# TML_Tick_Tacho_Timergrapher_Mic_v2.net
KiCad netlist of a schematic drawn in EAGLE
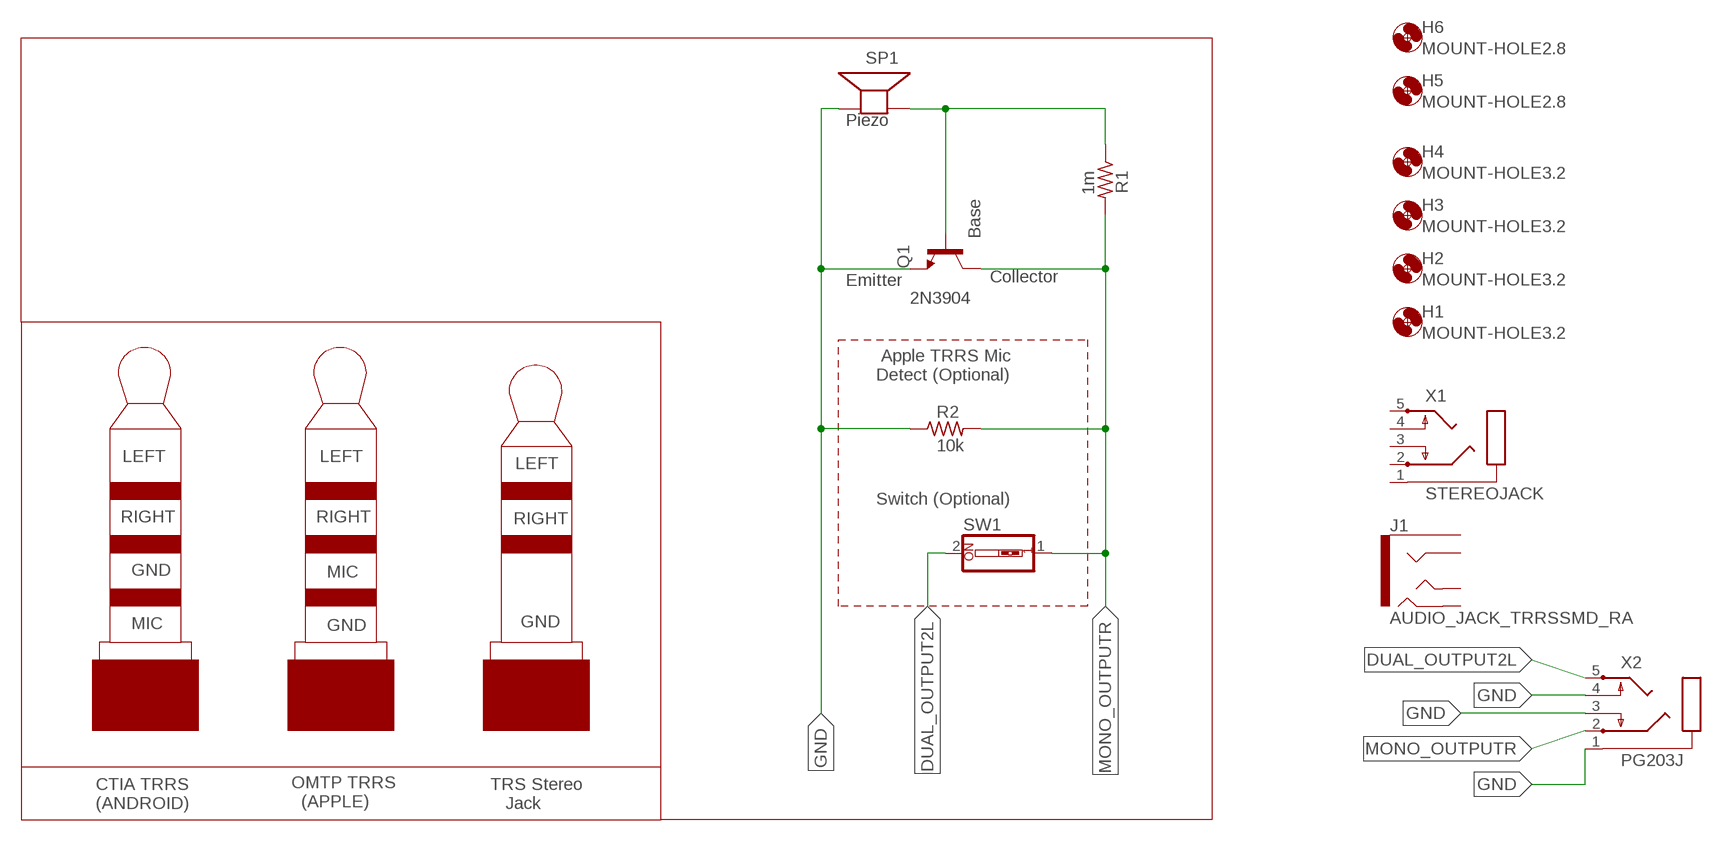
[diagram p0: schematic, sheet 1]

(export (version "E")
  (design (tool "Eeschema 10.0.6"))
  (components
    (comp (ref "H1")
      (value "MOUNT-HOLE3.2")
      (footprint "eagle-import:3,2")
      (libsource (lib "eagle-import") (part "MOUNT-HOLE3.2"))
    )
    (comp (ref "H2")
      (value "MOUNT-HOLE3.2")
      (footprint "eagle-import:3,2")
      (libsource (lib "eagle-import") (part "MOUNT-HOLE3.2"))
    )
    (comp (ref "H3")
      (value "MOUNT-HOLE3.2")
      (footprint "eagle-import:3,2")
      (libsource (lib "eagle-import") (part "MOUNT-HOLE3.2"))
    )
    (comp (ref "H4")
      (value "MOUNT-HOLE3.2")
      (footprint "eagle-import:3,2")
      (libsource (lib "eagle-import") (part "MOUNT-HOLE3.2"))
    )
    (comp (ref "H5")
      (value "MOUNT-HOLE2.8")
      (footprint "eagle-import:2,8")
      (libsource (lib "eagle-import") (part "MOUNT-HOLE2.8"))
    )
    (comp (ref "H6")
      (value "MOUNT-HOLE2.8")
      (footprint "eagle-import:2,8")
      (libsource (lib "eagle-import") (part "MOUNT-HOLE2.8"))
    )
    (comp (ref "J1")
      (value "AUDIO_JACK_TRRSSMD_RA")
      (footprint "eagle-import:AUDIO_JACK_3.5MM_TRRS_SMD_RA")
      (libsource (lib "eagle-import") (part "AUDIO_JACK_TRRSSMD_RA"))
    )
    (comp (ref "Q1")
      (value "2N3904")
      (footprint "eagle-import:TO92")
      (libsource (lib "eagle-import") (part "2N3904"))
    )
    (comp (ref "R1")
      (value "1m")
      (footprint "eagle-import:0204_7")
      (libsource (lib "eagle-import") (part "R-US_0204/7"))
    )
    (comp (ref "R2")
      (value "10k")
      (footprint "eagle-import:0204_7")
      (libsource (lib "eagle-import") (part "R-US_0204/7"))
    )
    (comp (ref "SP1")
      (value "Piezo")
      (footprint "eagle-import:AL60P")
      (libsource (lib "eagle-import") (part "SPEAKER/AL60P"))
    )
    (comp (ref "SW1")
      (value "SW_DIP-1")
      (footprint "eagle-import:EDG-01")
      (libsource (lib "eagle-import") (part "SW_DIP-1"))
    )
    (comp (ref "X1")
      (value "STEREOJACK")
      (footprint "eagle-import:STX3100")
      (libsource (lib "eagle-import") (part "STEREOJACK"))
    )
    (comp (ref "X2")
      (value "PG203J")
      (footprint "eagle-import:PG203J")
      (libsource (lib "eagle-import") (part "PG203J"))
    )
  )
  (nets
    (net (code "1") (name "DUAL_OUTPUT2L") (class "Default")
      (node (ref "SW1") (pin "2") (pinfunction "2_2") (pintype "passive"))
      (node (ref "X2") (pin "5") (pinfunction "5_5") (pintype "passive"))
    )
    (net (code "2") (name "GND") (class "Default")
      (node (ref "Q1") (pin "3") (pinfunction "E_3") (pintype "passive"))
      (node (ref "R2") (pin "1") (pinfunction "1_1") (pintype "passive"))
      (node (ref "SP1") (pin "1") (pinfunction "+_1") (pintype "passive"))
      (node (ref "X2") (pin "1") (pinfunction "1_1") (pintype "passive"))
      (node (ref "X2") (pin "3") (pinfunction "3_3") (pintype "passive"))
      (node (ref "X2") (pin "4") (pinfunction "4_4") (pintype "passive"))
    )
    (net (code "3") (name "MONO_OUTPUTR") (class "Default")
      (node (ref "Q1") (pin "1") (pinfunction "C_1") (pintype "passive"))
      (node (ref "R1") (pin "2") (pinfunction "2_2") (pintype "passive"))
      (node (ref "R2") (pin "2") (pinfunction "2_2") (pintype "passive"))
      (node (ref "SW1") (pin "1") (pinfunction "1_1") (pintype "passive"))
      (node (ref "X2") (pin "2") (pinfunction "2_2") (pintype "passive"))
    )
    (net (code "4") (name "Net-(Q1-B)") (class "Default")
      (node (ref "Q1") (pin "2") (pinfunction "B_2") (pintype "passive"))
      (node (ref "R1") (pin "1") (pinfunction "1_1") (pintype "passive"))
      (node (ref "SP1") (pin "2") (pinfunction "-_2") (pintype "passive"))
    )
    (net (code "5") (name "unconnected-(J1-PadEARTH)") (class "Default")
      (node (ref "J1") (pin "EARTH") (pinfunction "EARTH_EARTH") (pintype "bidirectional"))
    )
    (net (code "6") (name "unconnected-(J1-PadRING1)") (class "Default")
      (node (ref "J1") (pin "RING1") (pinfunction "RING1_RING1") (pintype "bidirectional"))
    )
    (net (code "7") (name "unconnected-(J1-PadRING2)") (class "Default")
      (node (ref "J1") (pin "RING2") (pinfunction "RING2_RING2") (pintype "bidirectional"))
    )
    (net (code "8") (name "unconnected-(J1-PadTIP)") (class "Default")
      (node (ref "J1") (pin "TIP") (pinfunction "TIP_TIP") (pintype "bidirectional"))
    )
    (net (code "9") (name "unconnected-(X1-Pad1)") (class "Default")
      (node (ref "X1") (pin "1") (pinfunction "1_1") (pintype "passive"))
    )
    (net (code "10") (name "unconnected-(X1-Pad2)") (class "Default")
      (node (ref "X1") (pin "2") (pinfunction "2_2") (pintype "passive"))
    )
    (net (code "11") (name "unconnected-(X1-Pad3)") (class "Default")
      (node (ref "X1") (pin "3") (pinfunction "3_3") (pintype "passive"))
    )
    (net (code "12") (name "unconnected-(X1-Pad4)") (class "Default")
      (node (ref "X1") (pin "4") (pinfunction "4_4") (pintype "passive"))
    )
    (net (code "13") (name "unconnected-(X1-Pad5)") (class "Default")
      (node (ref "X1") (pin "5") (pinfunction "5_5") (pintype "passive"))
    )
  )
)
